# POWER.net
KiCad netlist of a schematic drawn in EAGLE
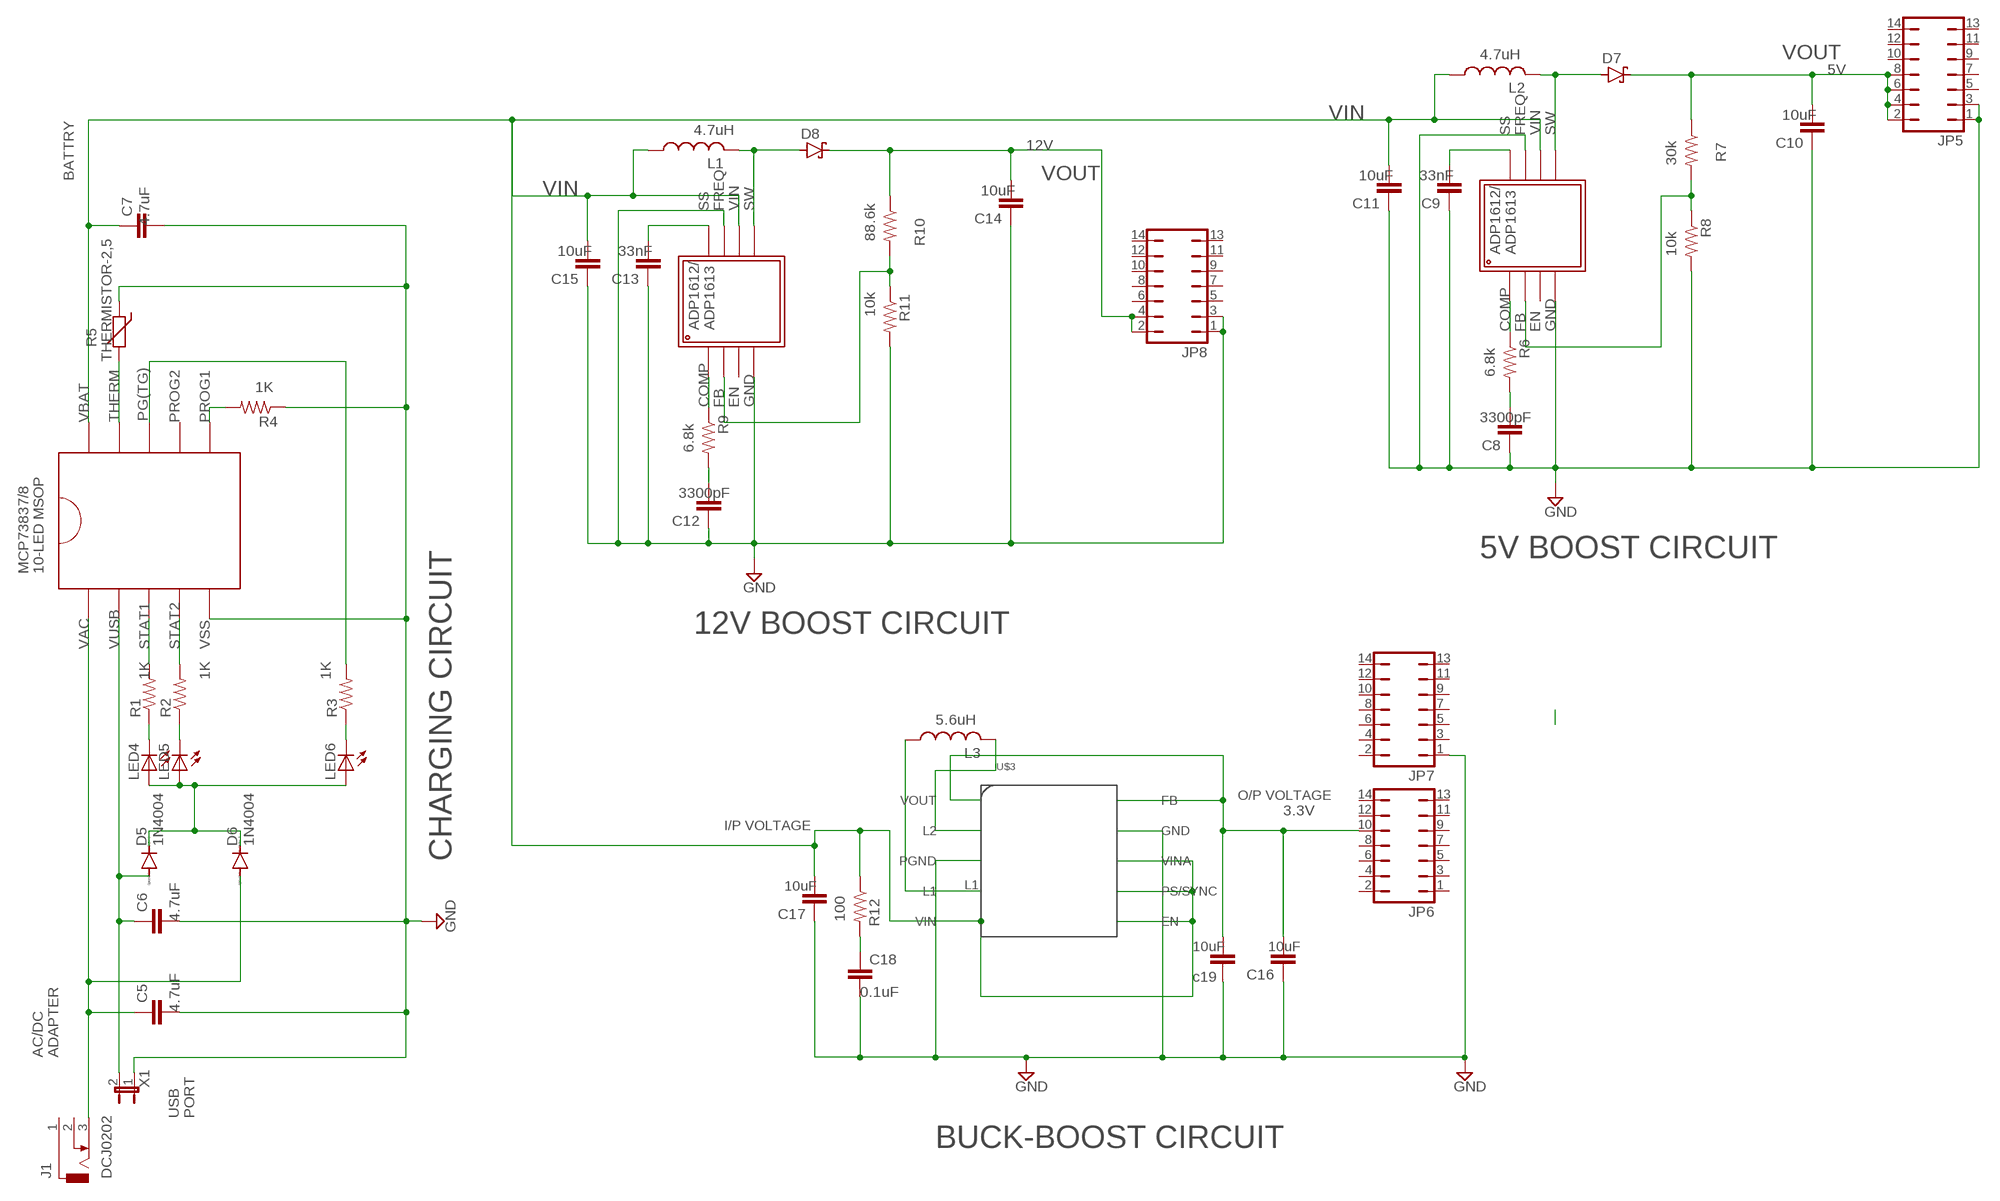
[diagram p0: schematic, sheet 1]

(export (version "E")
  (design (tool "Eeschema 10.0.6"))
  (components
    (comp (ref "C1")
      (value "C2,5-3")
      (footprint "eagle-import:C2.5-3")
      (libsource (lib "eagle-import") (part "C2,5-3"))
    )
    (comp (ref "C5")
      (value "C2.5/5")
      (footprint "eagle-import:C2.5-5")
      (libsource (lib "eagle-import") (part "C2.5/5"))
    )
    (comp (ref "C6")
      (value "C2.5/5")
      (footprint "eagle-import:C2.5-5")
      (libsource (lib "eagle-import") (part "C2.5/5"))
    )
    (comp (ref "C7")
      (value "C2.5/5")
      (footprint "eagle-import:C2.5-5")
      (libsource (lib "eagle-import") (part "C2.5/5"))
    )
    (comp (ref "C8")
      (value "C2,5-3")
      (footprint "eagle-import:C2.5-3")
      (libsource (lib "eagle-import") (part "C2,5-3"))
    )
    (comp (ref "C9")
      (value "C2,5-3")
      (footprint "eagle-import:C2.5-3")
      (libsource (lib "eagle-import") (part "C2,5-3"))
    )
    (comp (ref "C10")
      (value "C2,5-3")
      (footprint "eagle-import:C2.5-3")
      (libsource (lib "eagle-import") (part "C2,5-3"))
    )
    (comp (ref "C11")
      (value "C2,5-3")
      (footprint "eagle-import:C2.5-3")
      (libsource (lib "eagle-import") (part "C2,5-3"))
    )
    (comp (ref "C12")
      (value "C2,5-3")
      (footprint "eagle-import:C2.5-3")
      (libsource (lib "eagle-import") (part "C2,5-3"))
    )
    (comp (ref "C13")
      (value "C2,5-3")
      (footprint "eagle-import:C2.5-3")
      (libsource (lib "eagle-import") (part "C2,5-3"))
    )
    (comp (ref "C14")
      (value "C2,5-3")
      (footprint "eagle-import:C2.5-3")
      (libsource (lib "eagle-import") (part "C2,5-3"))
    )
    (comp (ref "C15")
      (value "C2,5-3")
      (footprint "eagle-import:C2.5-3")
      (libsource (lib "eagle-import") (part "C2,5-3"))
    )
    (comp (ref "C16")
      (value "C2,5-3")
      (footprint "eagle-import:C2.5-3")
      (libsource (lib "eagle-import") (part "C2,5-3"))
    )
    (comp (ref "C17")
      (value "C2,5-3")
      (footprint "eagle-import:C2.5-3")
      (libsource (lib "eagle-import") (part "C2,5-3"))
    )
    (comp (ref "C18")
      (value "C2,5-3")
      (footprint "eagle-import:C2.5-3")
      (libsource (lib "eagle-import") (part "C2,5-3"))
    )
    (comp (ref "D5")
      (value "1N4004")
      (footprint "eagle-import:DO41-10")
      (libsource (lib "eagle-import") (part "1N4004"))
    )
    (comp (ref "D6")
      (value "1N4004")
      (footprint "eagle-import:DO41-10")
      (libsource (lib "eagle-import") (part "1N4004"))
    )
    (comp (ref "D7")
      (value "SCHOTTKY-DIODEC4111-15")
      (footprint "eagle-import:C4111-15")
      (libsource (lib "eagle-import") (part "SCHOTTKY-DIODEC4111-15"))
    )
    (comp (ref "D8")
      (value "SCHOTTKY-DIODEC4111-15")
      (footprint "eagle-import:C4111-15")
      (libsource (lib "eagle-import") (part "SCHOTTKY-DIODEC4111-15"))
    )
    (comp (ref "J1")
      (value "DCJ0202")
      (footprint "eagle-import:DCJ0202")
      (libsource (lib "eagle-import") (part "DCJ0202"))
    )
    (comp (ref "JP1")
      (value "JP1E")
      (footprint "eagle-import:JP1")
      (libsource (lib "eagle-import") (part "JP1E"))
    )
    (comp (ref "JP5")
      (value "JP7Q")
      (footprint "eagle-import:JP7Q")
      (libsource (lib "eagle-import") (part "JP7Q"))
    )
    (comp (ref "JP6")
      (value "JP7Q")
      (footprint "eagle-import:JP7Q")
      (libsource (lib "eagle-import") (part "JP7Q"))
    )
    (comp (ref "JP7")
      (value "JP7Q")
      (footprint "eagle-import:JP7Q")
      (libsource (lib "eagle-import") (part "JP7Q"))
    )
    (comp (ref "JP8")
      (value "JP7Q")
      (footprint "eagle-import:JP7Q")
      (libsource (lib "eagle-import") (part "JP7Q"))
    )
    (comp (ref "L1")
      (value "L-US0204/5")
      (footprint "eagle-import:0204_5")
      (libsource (lib "eagle-import") (part "L-US0204/5"))
    )
    (comp (ref "L2")
      (value "L-US0204/5")
      (footprint "eagle-import:0204_5")
      (libsource (lib "eagle-import") (part "L-US0204/5"))
    )
    (comp (ref "L3")
      (value "L-US0204/5")
      (footprint "eagle-import:0204_5")
      (libsource (lib "eagle-import") (part "L-US0204/5"))
    )
    (comp (ref "LED4")
      (value "LED3MM")
      (footprint "eagle-import:LED3MM")
      (libsource (lib "eagle-import") (part "LED3MM"))
    )
    (comp (ref "LED5")
      (value "LED3MM")
      (footprint "eagle-import:LED3MM")
      (libsource (lib "eagle-import") (part "LED3MM"))
    )
    (comp (ref "LED6")
      (value "LED3MM")
      (footprint "eagle-import:LED3MM")
      (libsource (lib "eagle-import") (part "LED3MM"))
    )
    (comp (ref "R1")
      (value "R-US_0204/2V")
      (footprint "eagle-import:0204V")
      (libsource (lib "eagle-import") (part "R-US_0204/2V"))
    )
    (comp (ref "R2")
      (value "R-US_0204/2V")
      (footprint "eagle-import:0204V")
      (libsource (lib "eagle-import") (part "R-US_0204/2V"))
    )
    (comp (ref "R3")
      (value "R-US_0204/2V")
      (footprint "eagle-import:0204V")
      (libsource (lib "eagle-import") (part "R-US_0204/2V"))
    )
    (comp (ref "R4")
      (value "R-US_0204/2V")
      (footprint "eagle-import:0204V")
      (libsource (lib "eagle-import") (part "R-US_0204/2V"))
    )
    (comp (ref "R5")
      (value "THERMISTOR-2,5")
      (footprint "eagle-import:RS-2,5")
      (libsource (lib "eagle-import") (part "THERMISTOR-2,5"))
    )
    (comp (ref "R6")
      (value "R-US_0204/2V")
      (footprint "eagle-import:0204V")
      (libsource (lib "eagle-import") (part "R-US_0204/2V"))
    )
    (comp (ref "R7")
      (value "R-US_0204/2V")
      (footprint "eagle-import:0204V")
      (libsource (lib "eagle-import") (part "R-US_0204/2V"))
    )
    (comp (ref "R8")
      (value "R-US_0204/2V")
      (footprint "eagle-import:0204V")
      (libsource (lib "eagle-import") (part "R-US_0204/2V"))
    )
    (comp (ref "R9")
      (value "R-US_0204/2V")
      (footprint "eagle-import:0204V")
      (libsource (lib "eagle-import") (part "R-US_0204/2V"))
    )
    (comp (ref "R10")
      (value "R-US_0204/2V")
      (footprint "eagle-import:0204V")
      (libsource (lib "eagle-import") (part "R-US_0204/2V"))
    )
    (comp (ref "R11")
      (value "R-US_0204/2V")
      (footprint "eagle-import:0204V")
      (libsource (lib "eagle-import") (part "R-US_0204/2V"))
    )
    (comp (ref "R12")
      (value "R-US_0204/2V")
      (footprint "eagle-import:0204V")
      (libsource (lib "eagle-import") (part "R-US_0204/2V"))
    )
    (comp (ref "U$1")
      (value "ADP1612")
      (footprint "eagle-import:ADP1612")
      (libsource (lib "eagle-import") (part "ADP1612"))
    )
    (comp (ref "U$2")
      (value "ADP1612")
      (footprint "eagle-import:ADP1612")
      (libsource (lib "eagle-import") (part "ADP1612"))
    )
    (comp (ref "U$3")
      (value "TPS63002")
      (footprint "eagle-import:TPS63002")
      (libsource (lib "eagle-import") (part "TPS63002"))
    )
    (comp (ref "U$4")
      (value "MCP73837/8")
      (footprint "eagle-import:MCP73837_8")
      (libsource (lib "eagle-import") (part "MCP73837/8"))
    )
  )
  (nets
    (net (code "1") (name "GND") (class "Default")
      (node (ref "C1") (pin "1") (pinfunction "1_1") (pintype "passive"))
      (node (ref "C10") (pin "1") (pinfunction "1_1") (pintype "passive"))
      (node (ref "C11") (pin "1") (pinfunction "1_1") (pintype "passive"))
      (node (ref "C12") (pin "1") (pinfunction "1_1") (pintype "passive"))
      (node (ref "C13") (pin "1") (pinfunction "1_1") (pintype "passive"))
      (node (ref "C14") (pin "1") (pinfunction "1_1") (pintype "passive"))
      (node (ref "C15") (pin "1") (pinfunction "1_1") (pintype "passive"))
      (node (ref "C16") (pin "1") (pinfunction "1_1") (pintype "passive"))
      (node (ref "C17") (pin "1") (pinfunction "1_1") (pintype "passive"))
      (node (ref "C18") (pin "2") (pinfunction "2_2") (pintype "passive"))
      (node (ref "C5") (pin "2") (pinfunction "2_2") (pintype "passive"))
      (node (ref "C6") (pin "2") (pinfunction "2_2") (pintype "passive"))
      (node (ref "C7") (pin "2") (pinfunction "2_2") (pintype "passive"))
      (node (ref "C8") (pin "1") (pinfunction "1_1") (pintype "passive"))
      (node (ref "C9") (pin "1") (pinfunction "1_1") (pintype "passive"))
      (node (ref "JP1") (pin "1") (pinfunction "1_1") (pintype "passive"))
      (node (ref "JP5") (pin "1") (pinfunction "1_1") (pintype "passive"))
      (node (ref "JP5") (pin "3") (pinfunction "3_3") (pintype "passive"))
      (node (ref "JP7") (pin "1") (pinfunction "1_1") (pintype "passive"))
      (node (ref "JP8") (pin "1") (pinfunction "1_1") (pintype "passive"))
      (node (ref "JP8") (pin "3") (pinfunction "3_3") (pintype "passive"))
      (node (ref "R11") (pin "2") (pinfunction "2_2") (pintype "passive"))
      (node (ref "R4") (pin "1") (pinfunction "1_1") (pintype "passive"))
      (node (ref "R5") (pin "1") (pinfunction "1_1") (pintype "passive"))
      (node (ref "R8") (pin "2") (pinfunction "2_2") (pintype "passive"))
      (node (ref "U$1") (pin "P$4") (pinfunction "P$4_P$4") (pintype "bidirectional"))
      (node (ref "U$1") (pin "P$6") (pinfunction "P$6_P$6") (pintype "bidirectional"))
      (node (ref "U$2") (pin "P$4") (pinfunction "P$4_P$4") (pintype "bidirectional"))
      (node (ref "U$2") (pin "P$6") (pinfunction "P$6_P$6") (pintype "bidirectional"))
      (node (ref "U$3") (pin "GND") (pinfunction "GND_GND") (pintype "bidirectional"))
      (node (ref "U$3") (pin "PGND") (pinfunction "PGND_PGND") (pintype "bidirectional"))
      (node (ref "U$4") (pin "P$5") (pinfunction "P$5_P$5") (pintype "bidirectional"))
    )
    (net (code "2") (name "Net-(C1-Pad2)") (class "Default")
      (node (ref "C1") (pin "2") (pinfunction "2_2") (pintype "passive"))
      (node (ref "C16") (pin "2") (pinfunction "2_2") (pintype "passive"))
      (node (ref "JP6") (pin "10") (pinfunction "10_10") (pintype "passive"))
      (node (ref "U$3") (pin "FB") (pinfunction "FB_FB") (pintype "bidirectional"))
      (node (ref "U$3") (pin "VOUT") (pinfunction "VOUT_VOUT") (pintype "bidirectional"))
    )
    (net (code "3") (name "Net-(C5-Pad1)") (class "Default")
      (node (ref "C5") (pin "1") (pinfunction "1_1") (pintype "passive"))
      (node (ref "D6") (pin "A") (pinfunction "A_A") (pintype "passive"))
      (node (ref "J1") (pin "3") (pinfunction "3_3") (pintype "passive"))
      (node (ref "U$4") (pin "P$1") (pinfunction "P$1_P$1") (pintype "bidirectional"))
    )
    (net (code "4") (name "Net-(C6-Pad1)") (class "Default")
      (node (ref "C6") (pin "1") (pinfunction "1_1") (pintype "passive"))
      (node (ref "D5") (pin "A") (pinfunction "A_A") (pintype "passive"))
      (node (ref "JP1") (pin "2") (pinfunction "2_2") (pintype "passive"))
      (node (ref "U$4") (pin "P$2") (pinfunction "P$2_P$2") (pintype "bidirectional"))
    )
    (net (code "5") (name "Net-(C8-Pad2)") (class "Default")
      (node (ref "C8") (pin "2") (pinfunction "2_2") (pintype "passive"))
      (node (ref "R6") (pin "2") (pinfunction "2_2") (pintype "passive"))
    )
    (net (code "6") (name "Net-(C9-Pad2)") (class "Default")
      (node (ref "C9") (pin "2") (pinfunction "2_2") (pintype "passive"))
      (node (ref "U$1") (pin "P$5") (pinfunction "P$5_P$5") (pintype "bidirectional"))
    )
    (net (code "7") (name "Net-(C10-Pad2)") (class "Default")
      (node (ref "C10") (pin "2") (pinfunction "2_2") (pintype "passive"))
      (node (ref "D7") (pin "C") (pinfunction "C_C") (pintype "passive"))
      (node (ref "JP5") (pin "2") (pinfunction "2_2") (pintype "passive"))
      (node (ref "JP5") (pin "4") (pinfunction "4_4") (pintype "passive"))
      (node (ref "JP5") (pin "6") (pinfunction "6_6") (pintype "passive"))
      (node (ref "JP5") (pin "8") (pinfunction "8_8") (pintype "passive"))
      (node (ref "R7") (pin "1") (pinfunction "1_1") (pintype "passive"))
    )
    (net (code "8") (name "Net-(C11-Pad2)") (class "Default")
      (node (ref "C11") (pin "2") (pinfunction "2_2") (pintype "passive"))
      (node (ref "C15") (pin "2") (pinfunction "2_2") (pintype "passive"))
      (node (ref "C17") (pin "2") (pinfunction "2_2") (pintype "passive"))
      (node (ref "C7") (pin "1") (pinfunction "1_1") (pintype "passive"))
      (node (ref "L1") (pin "1") (pinfunction "1_1") (pintype "passive"))
      (node (ref "L2") (pin "1") (pinfunction "1_1") (pintype "passive"))
      (node (ref "R12") (pin "1") (pinfunction "1_1") (pintype "passive"))
      (node (ref "U$1") (pin "P$7") (pinfunction "P$7_P$7") (pintype "bidirectional"))
      (node (ref "U$2") (pin "P$7") (pinfunction "P$7_P$7") (pintype "bidirectional"))
      (node (ref "U$3") (pin "EN") (pinfunction "EN_EN") (pintype "bidirectional"))
      (node (ref "U$3") (pin "PS/SYNC") (pinfunction "PS/SYNC_PS/SYNC") (pintype "bidirectional"))
      (node (ref "U$3") (pin "VIN") (pinfunction "VIN_VIN") (pintype "bidirectional"))
      (node (ref "U$3") (pin "VINA") (pinfunction "VINA_VINA") (pintype "bidirectional"))
      (node (ref "U$4") (pin "P$10") (pinfunction "P$10_P$10") (pintype "bidirectional"))
    )
    (net (code "9") (name "Net-(C12-Pad2)") (class "Default")
      (node (ref "C12") (pin "2") (pinfunction "2_2") (pintype "passive"))
      (node (ref "R9") (pin "2") (pinfunction "2_2") (pintype "passive"))
    )
    (net (code "10") (name "Net-(C13-Pad2)") (class "Default")
      (node (ref "C13") (pin "2") (pinfunction "2_2") (pintype "passive"))
      (node (ref "U$2") (pin "P$5") (pinfunction "P$5_P$5") (pintype "bidirectional"))
    )
    (net (code "11") (name "Net-(C14-Pad2)") (class "Default")
      (node (ref "C14") (pin "2") (pinfunction "2_2") (pintype "passive"))
      (node (ref "D8") (pin "C") (pinfunction "C_C") (pintype "passive"))
      (node (ref "JP8") (pin "2") (pinfunction "2_2") (pintype "passive"))
      (node (ref "JP8") (pin "4") (pinfunction "4_4") (pintype "passive"))
      (node (ref "R10") (pin "1") (pinfunction "1_1") (pintype "passive"))
    )
    (net (code "12") (name "Net-(C18-Pad1)") (class "Default")
      (node (ref "C18") (pin "1") (pinfunction "1_1") (pintype "passive"))
      (node (ref "R12") (pin "2") (pinfunction "2_2") (pintype "passive"))
    )
    (net (code "13") (name "Net-(D5-PadC)") (class "Default")
      (node (ref "D5") (pin "C") (pinfunction "C_C") (pintype "passive"))
      (node (ref "D6") (pin "C") (pinfunction "C_C") (pintype "passive"))
      (node (ref "LED4") (pin "A") (pinfunction "A_A") (pintype "passive"))
      (node (ref "LED5") (pin "A") (pinfunction "A_A") (pintype "passive"))
      (node (ref "LED6") (pin "A") (pinfunction "A_A") (pintype "passive"))
    )
    (net (code "14") (name "Net-(D7-PadA)") (class "Default")
      (node (ref "D7") (pin "A") (pinfunction "A_A") (pintype "passive"))
      (node (ref "L2") (pin "2") (pinfunction "2_2") (pintype "passive"))
      (node (ref "U$1") (pin "P$8") (pinfunction "P$8_P$8") (pintype "bidirectional"))
    )
    (net (code "15") (name "Net-(D8-PadA)") (class "Default")
      (node (ref "D8") (pin "A") (pinfunction "A_A") (pintype "passive"))
      (node (ref "L1") (pin "2") (pinfunction "2_2") (pintype "passive"))
      (node (ref "U$2") (pin "P$8") (pinfunction "P$8_P$8") (pintype "bidirectional"))
    )
    (net (code "16") (name "Net-(L3-Pad1)") (class "Default")
      (node (ref "L3") (pin "1") (pinfunction "1_1") (pintype "passive"))
      (node (ref "U$3") (pin "L1") (pinfunction "L1_L1") (pintype "bidirectional"))
    )
    (net (code "17") (name "Net-(L3-Pad2)") (class "Default")
      (node (ref "L3") (pin "2") (pinfunction "2_2") (pintype "passive"))
      (node (ref "U$3") (pin "L2") (pinfunction "L2_L2") (pintype "bidirectional"))
    )
    (net (code "18") (name "Net-(LED4-C)") (class "Default")
      (node (ref "LED4") (pin "K") (pinfunction "C_K") (pintype "passive"))
      (node (ref "R1") (pin "1") (pinfunction "1_1") (pintype "passive"))
    )
    (net (code "19") (name "Net-(LED5-C)") (class "Default")
      (node (ref "LED5") (pin "K") (pinfunction "C_K") (pintype "passive"))
      (node (ref "R2") (pin "1") (pinfunction "1_1") (pintype "passive"))
    )
    (net (code "20") (name "Net-(LED6-C)") (class "Default")
      (node (ref "LED6") (pin "K") (pinfunction "C_K") (pintype "passive"))
      (node (ref "R3") (pin "1") (pinfunction "1_1") (pintype "passive"))
    )
    (net (code "21") (name "Net-(R1-Pad2)") (class "Default")
      (node (ref "R1") (pin "2") (pinfunction "2_2") (pintype "passive"))
      (node (ref "U$4") (pin "P$3") (pinfunction "P$3_P$3") (pintype "bidirectional"))
    )
    (net (code "22") (name "Net-(R2-Pad2)") (class "Default")
      (node (ref "R2") (pin "2") (pinfunction "2_2") (pintype "passive"))
      (node (ref "U$4") (pin "P$4") (pinfunction "P$4_P$4") (pintype "bidirectional"))
    )
    (net (code "23") (name "Net-(R3-Pad2)") (class "Default")
      (node (ref "R3") (pin "2") (pinfunction "2_2") (pintype "passive"))
      (node (ref "U$4") (pin "P$8") (pinfunction "P$8_P$8") (pintype "bidirectional"))
    )
    (net (code "24") (name "Net-(R4-Pad2)") (class "Default")
      (node (ref "R4") (pin "2") (pinfunction "2_2") (pintype "passive"))
      (node (ref "U$4") (pin "P$6") (pinfunction "P$6_P$6") (pintype "bidirectional"))
    )
    (net (code "25") (name "Net-(R5-Pad2)") (class "Default")
      (node (ref "R5") (pin "2") (pinfunction "2_2") (pintype "passive"))
      (node (ref "U$4") (pin "P$9") (pinfunction "P$9_P$9") (pintype "bidirectional"))
    )
    (net (code "26") (name "Net-(R6-Pad1)") (class "Default")
      (node (ref "R6") (pin "1") (pinfunction "1_1") (pintype "passive"))
      (node (ref "U$1") (pin "P$1") (pinfunction "P$1_P$1") (pintype "bidirectional"))
    )
    (net (code "27") (name "Net-(R7-Pad2)") (class "Default")
      (node (ref "R7") (pin "2") (pinfunction "2_2") (pintype "passive"))
      (node (ref "R8") (pin "1") (pinfunction "1_1") (pintype "passive"))
      (node (ref "U$1") (pin "P$2") (pinfunction "P$2_P$2") (pintype "bidirectional"))
    )
    (net (code "28") (name "Net-(R9-Pad1)") (class "Default")
      (node (ref "R9") (pin "1") (pinfunction "1_1") (pintype "passive"))
      (node (ref "U$2") (pin "P$1") (pinfunction "P$1_P$1") (pintype "bidirectional"))
    )
    (net (code "29") (name "Net-(R10-Pad2)") (class "Default")
      (node (ref "R10") (pin "2") (pinfunction "2_2") (pintype "passive"))
      (node (ref "R11") (pin "1") (pinfunction "1_1") (pintype "passive"))
      (node (ref "U$2") (pin "P$2") (pinfunction "P$2_P$2") (pintype "bidirectional"))
    )
    (net (code "30") (name "unconnected-(J1-Pad1)") (class "Default")
      (node (ref "J1") (pin "1") (pinfunction "1_1") (pintype "passive"))
    )
    (net (code "31") (name "unconnected-(J1-Pad2)") (class "Default")
      (node (ref "J1") (pin "2") (pinfunction "2_2") (pintype "passive"))
    )
    (net (code "32") (name "unconnected-(JP5-Pad5)") (class "Default")
      (node (ref "JP5") (pin "5") (pinfunction "5_5") (pintype "passive"))
    )
    (net (code "33") (name "unconnected-(JP5-Pad7)") (class "Default")
      (node (ref "JP5") (pin "7") (pinfunction "7_7") (pintype "passive"))
    )
    (net (code "34") (name "unconnected-(JP5-Pad9)") (class "Default")
      (node (ref "JP5") (pin "9") (pinfunction "9_9") (pintype "passive"))
    )
    (net (code "35") (name "unconnected-(JP5-Pad10)") (class "Default")
      (node (ref "JP5") (pin "10") (pinfunction "10_10") (pintype "passive"))
    )
    (net (code "36") (name "unconnected-(JP5-Pad11)") (class "Default")
      (node (ref "JP5") (pin "11") (pinfunction "11_11") (pintype "passive"))
    )
    (net (code "37") (name "unconnected-(JP5-Pad12)") (class "Default")
      (node (ref "JP5") (pin "12") (pinfunction "12_12") (pintype "passive"))
    )
    (net (code "38") (name "unconnected-(JP5-Pad13)") (class "Default")
      (node (ref "JP5") (pin "13") (pinfunction "13_13") (pintype "passive"))
    )
    (net (code "39") (name "unconnected-(JP5-Pad14)") (class "Default")
      (node (ref "JP5") (pin "14") (pinfunction "14_14") (pintype "passive"))
    )
    (net (code "40") (name "unconnected-(JP6-Pad1)") (class "Default")
      (node (ref "JP6") (pin "1") (pinfunction "1_1") (pintype "passive"))
    )
    (net (code "41") (name "unconnected-(JP6-Pad2)") (class "Default")
      (node (ref "JP6") (pin "2") (pinfunction "2_2") (pintype "passive"))
    )
    (net (code "42") (name "unconnected-(JP6-Pad3)") (class "Default")
      (node (ref "JP6") (pin "3") (pinfunction "3_3") (pintype "passive"))
    )
    (net (code "43") (name "unconnected-(JP6-Pad4)") (class "Default")
      (node (ref "JP6") (pin "4") (pinfunction "4_4") (pintype "passive"))
    )
    (net (code "44") (name "unconnected-(JP6-Pad5)") (class "Default")
      (node (ref "JP6") (pin "5") (pinfunction "5_5") (pintype "passive"))
    )
    (net (code "45") (name "unconnected-(JP6-Pad6)") (class "Default")
      (node (ref "JP6") (pin "6") (pinfunction "6_6") (pintype "passive"))
    )
    (net (code "46") (name "unconnected-(JP6-Pad7)") (class "Default")
      (node (ref "JP6") (pin "7") (pinfunction "7_7") (pintype "passive"))
    )
    (net (code "47") (name "unconnected-(JP6-Pad8)") (class "Default")
      (node (ref "JP6") (pin "8") (pinfunction "8_8") (pintype "passive"))
    )
    (net (code "48") (name "unconnected-(JP6-Pad9)") (class "Default")
      (node (ref "JP6") (pin "9") (pinfunction "9_9") (pintype "passive"))
    )
    (net (code "49") (name "unconnected-(JP6-Pad11)") (class "Default")
      (node (ref "JP6") (pin "11") (pinfunction "11_11") (pintype "passive"))
    )
    (net (code "50") (name "unconnected-(JP6-Pad12)") (class "Default")
      (node (ref "JP6") (pin "12") (pinfunction "12_12") (pintype "passive"))
    )
    (net (code "51") (name "unconnected-(JP6-Pad13)") (class "Default")
      (node (ref "JP6") (pin "13") (pinfunction "13_13") (pintype "passive"))
    )
    (net (code "52") (name "unconnected-(JP6-Pad14)") (class "Default")
      (node (ref "JP6") (pin "14") (pinfunction "14_14") (pintype "passive"))
    )
    (net (code "53") (name "unconnected-(JP7-Pad2)") (class "Default")
      (node (ref "JP7") (pin "2") (pinfunction "2_2") (pintype "passive"))
    )
    (net (code "54") (name "unconnected-(JP7-Pad3)") (class "Default")
      (node (ref "JP7") (pin "3") (pinfunction "3_3") (pintype "passive"))
    )
    (net (code "55") (name "unconnected-(JP7-Pad4)") (class "Default")
      (node (ref "JP7") (pin "4") (pinfunction "4_4") (pintype "passive"))
    )
    (net (code "56") (name "unconnected-(JP7-Pad5)") (class "Default")
      (node (ref "JP7") (pin "5") (pinfunction "5_5") (pintype "passive"))
    )
    (net (code "57") (name "unconnected-(JP7-Pad6)") (class "Default")
      (node (ref "JP7") (pin "6") (pinfunction "6_6") (pintype "passive"))
    )
    (net (code "58") (name "unconnected-(JP7-Pad7)") (class "Default")
      (node (ref "JP7") (pin "7") (pinfunction "7_7") (pintype "passive"))
    )
    (net (code "59") (name "unconnected-(JP7-Pad8)") (class "Default")
      (node (ref "JP7") (pin "8") (pinfunction "8_8") (pintype "passive"))
    )
    (net (code "60") (name "unconnected-(JP7-Pad9)") (class "Default")
      (node (ref "JP7") (pin "9") (pinfunction "9_9") (pintype "passive"))
    )
    (net (code "61") (name "unconnected-(JP7-Pad10)") (class "Default")
      (node (ref "JP7") (pin "10") (pinfunction "10_10") (pintype "passive"))
    )
    (net (code "62") (name "unconnected-(JP7-Pad11)") (class "Default")
      (node (ref "JP7") (pin "11") (pinfunction "11_11") (pintype "passive"))
    )
    (net (code "63") (name "unconnected-(JP7-Pad12)") (class "Default")
      (node (ref "JP7") (pin "12") (pinfunction "12_12") (pintype "passive"))
    )
    (net (code "64") (name "unconnected-(JP7-Pad13)") (class "Default")
      (node (ref "JP7") (pin "13") (pinfunction "13_13") (pintype "passive"))
    )
    (net (code "65") (name "unconnected-(JP7-Pad14)") (class "Default")
      (node (ref "JP7") (pin "14") (pinfunction "14_14") (pintype "passive"))
    )
    (net (code "66") (name "unconnected-(JP8-Pad5)") (class "Default")
      (node (ref "JP8") (pin "5") (pinfunction "5_5") (pintype "passive"))
    )
    (net (code "67") (name "unconnected-(JP8-Pad6)") (class "Default")
      (node (ref "JP8") (pin "6") (pinfunction "6_6") (pintype "passive"))
    )
    (net (code "68") (name "unconnected-(JP8-Pad7)") (class "Default")
      (node (ref "JP8") (pin "7") (pinfunction "7_7") (pintype "passive"))
    )
    (net (code "69") (name "unconnected-(JP8-Pad8)") (class "Default")
      (node (ref "JP8") (pin "8") (pinfunction "8_8") (pintype "passive"))
    )
    (net (code "70") (name "unconnected-(JP8-Pad9)") (class "Default")
      (node (ref "JP8") (pin "9") (pinfunction "9_9") (pintype "passive"))
    )
    (net (code "71") (name "unconnected-(JP8-Pad10)") (class "Default")
      (node (ref "JP8") (pin "10") (pinfunction "10_10") (pintype "passive"))
    )
    (net (code "72") (name "unconnected-(JP8-Pad11)") (class "Default")
      (node (ref "JP8") (pin "11") (pinfunction "11_11") (pintype "passive"))
    )
    (net (code "73") (name "unconnected-(JP8-Pad12)") (class "Default")
      (node (ref "JP8") (pin "12") (pinfunction "12_12") (pintype "passive"))
    )
    (net (code "74") (name "unconnected-(JP8-Pad13)") (class "Default")
      (node (ref "JP8") (pin "13") (pinfunction "13_13") (pintype "passive"))
    )
    (net (code "75") (name "unconnected-(JP8-Pad14)") (class "Default")
      (node (ref "JP8") (pin "14") (pinfunction "14_14") (pintype "passive"))
    )
    (net (code "76") (name "unconnected-(U$1-PadP$3)") (class "Default")
      (node (ref "U$1") (pin "P$3") (pinfunction "P$3_P$3") (pintype "bidirectional"))
    )
    (net (code "77") (name "unconnected-(U$2-PadP$3)") (class "Default")
      (node (ref "U$2") (pin "P$3") (pinfunction "P$3_P$3") (pintype "bidirectional"))
    )
    (net (code "78") (name "unconnected-(U$4-PadP$7)") (class "Default")
      (node (ref "U$4") (pin "P$7") (pinfunction "P$7_P$7") (pintype "bidirectional"))
    )
  )
)
